# dw1000.net
KiCad netlist of a schematic drawn in Altium Designer
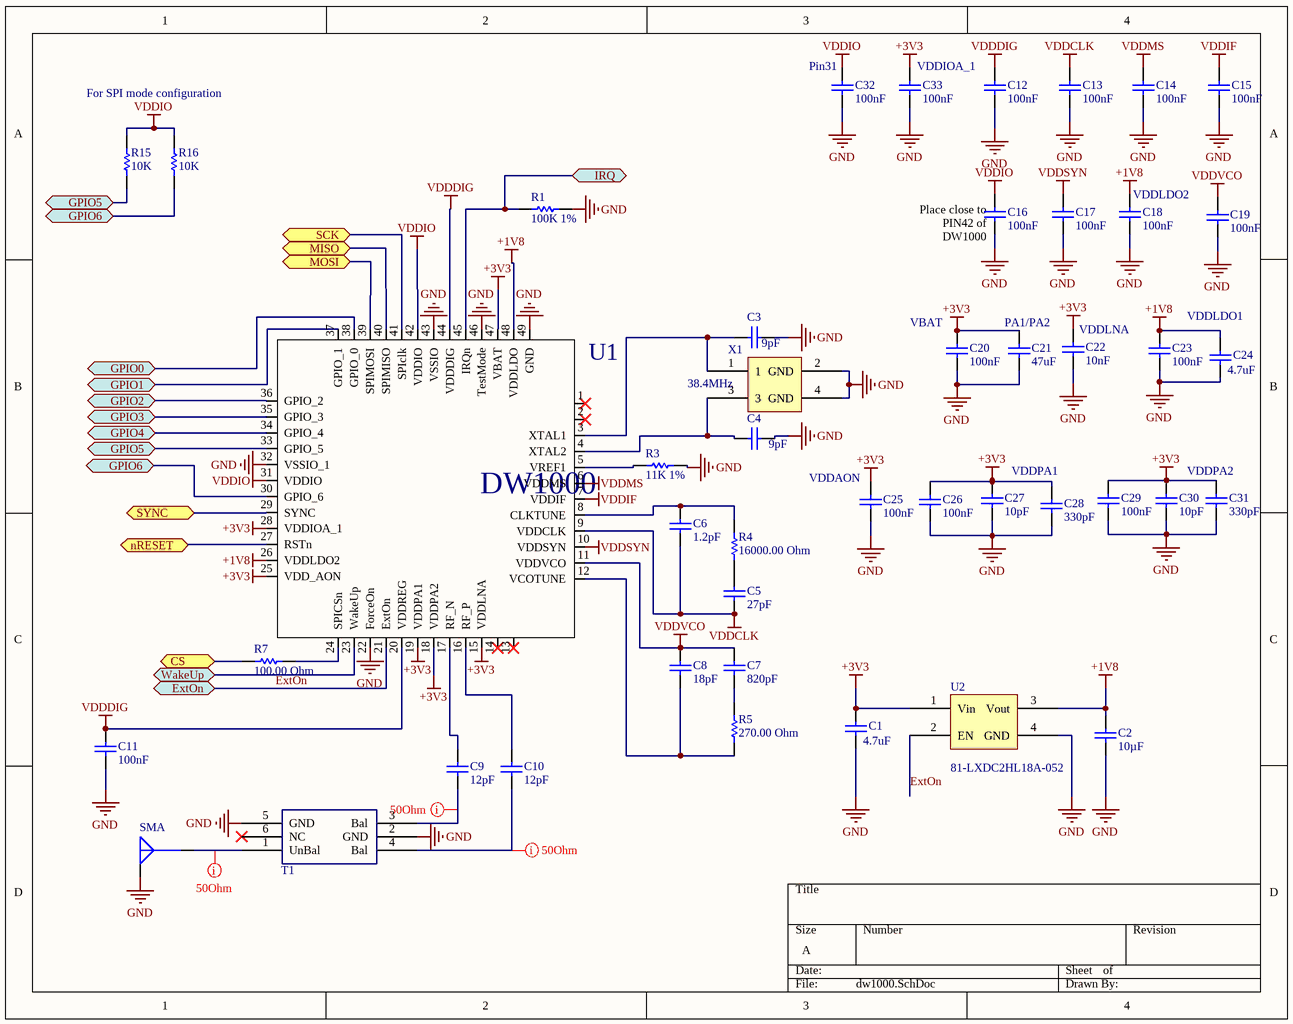
[diagram p0: dw1000.SchDoc]

(export (version "E")
  (design (tool "Eeschema 10.0.6"))
  (components
    (comp (ref "C1")
      (value "4.7uF")
      (footprint "CAPC0603(1608)100_M")
      (description "CAP 4.7uF 6.3V ±10% 0603 (1608 Metric) Thickness 1mm SMD")
      (fields (field (name "TOLERANCE") "Â±10%"))
      (libsource (lib "Altium Content Vault") (part "CMP-1035-02780-1"))
    )
    (comp (ref "C2")
      (value "10µF")
      (footprint "CAPC1608X100X35ML20T25")
      (fields (field (name "TOLERANCE") "±20%") (field (name "MANUFACTURER") "Taiyo Yuden"))
      (libsource (lib "Altium Content Vault") (part "CMP-2000-05443-1"))
    )
    (comp (ref "C3")
      (value "9pF")
      (footprint "CAPC0402(1005)60_L")
      (description "CAP 9pF 50V ±0.05pF 0402 (1005 Metric) Thickness 0.6mm SMD")
      (fields (field (name "TOLERANCE") "Â±0.05pF"))
      (libsource (lib "Altium Content Vault") (part "CAP"))
    )
    (comp (ref "C4")
      (value "9pF")
      (footprint "CAPC0402(1005)60_L")
      (description "CAP 9pF 50V ±0.05pF 0402 (1005 Metric) Thickness 0.6mm SMD")
      (fields (field (name "TOLERANCE") "Â±0.05pF"))
      (libsource (lib "Altium Content Vault") (part "CAP"))
    )
    (comp (ref "C5")
      (value "27pF")
      (footprint "CAPC0402(1005)60_L")
      (description "CAP 27pF 50V ±2% 0402 (1005 Metric) Thickness 0.6mm SMD")
      (fields (field (name "TOLERANCE") "Â±2%"))
      (libsource (lib "Altium Content Vault") (part "CMP-1034-00961-1"))
    )
    (comp (ref "C6")
      (value "1.2pF")
      (footprint "CAPC0402(1005)60_L")
      (description "CAP 1.2pF 50V ±0.05pF 0402 (1005 Metric) Thickness 0.6mm SMD")
      (fields (field (name "TOLERANCE") "Â±0.05pF"))
      (libsource (lib "Altium Content Vault") (part "CMP-1034-00083-1"))
    )
    (comp (ref "C7")
      (value "820pF")
      (footprint "CAPC0402(1005)60_L")
      (description "CAP 820pF 50V ±2% 0402 (1005 Metric) Thickness 0.6mm SMD")
      (fields (field (name "TOLERANCE") "Â±2%"))
      (libsource (lib "Altium Content Vault") (part "CMP-1034-01592-1"))
    )
    (comp (ref "C8")
      (value "18pF")
      (footprint "CAPC0402(1005)60_L")
      (description "CAP 18pF 50V ±2% 0402 (1005 Metric) Thickness 0.6mm SMD")
      (fields (field (name "TOLERANCE") "Â±2%"))
      (libsource (lib "Altium Content Vault") (part "CMP-1034-00863-1"))
    )
    (comp (ref "C9")
      (value "12pF")
      (footprint "CAPC0402(1005)60_L")
      (description "CAP 12pF 50V ±2% 0402 (1005 Metric) Thickness 0.6mm SMD")
      (fields (field (name "TOLERANCE") "Â±2%"))
      (libsource (lib "Altium Content Vault") (part "CAP"))
    )
    (comp (ref "C10")
      (value "12pF")
      (footprint "CAPC0402(1005)60_L")
      (description "CAP 12pF 50V ±2% 0402 (1005 Metric) Thickness 0.6mm SMD")
      (fields (field (name "TOLERANCE") "Â±2%"))
      (libsource (lib "Altium Content Vault") (part "CMP-1034-00768-1"))
    )
    (comp (ref "C11")
      (value "100nF")
      (footprint "CAPC0402(1005)60_L")
      (description "CAP 100nF 16V ±10% 0402 (1005 Metric) Thickness 0.6mm SMD")
      (fields (field (name "TOLERANCE") "Â±10%"))
      (libsource (lib "Altium Content Vault") (part "CMP-1034-02069-1"))
    )
    (comp (ref "C12")
      (value "100nF")
      (footprint "CAPC0402(1005)60_L")
      (description "CAP 100nF 16V ±10% 0402 (1005 Metric) Thickness 0.6mm SMD")
      (fields (field (name "TOLERANCE") "Â±10%"))
      (libsource (lib "Altium Content Vault") (part "CMP-1034-02069-1"))
    )
    (comp (ref "C13")
      (value "100nF")
      (footprint "CAPC0402(1005)60_L")
      (description "CAP 100nF 16V ±10% 0402 (1005 Metric) Thickness 0.6mm SMD")
      (fields (field (name "TOLERANCE") "Â±10%"))
      (libsource (lib "Altium Content Vault") (part "CMP-1034-02069-1"))
    )
    (comp (ref "C14")
      (value "100nF")
      (footprint "CAPC0402(1005)60_L")
      (description "CAP 100nF 16V ±10% 0402 (1005 Metric) Thickness 0.6mm SMD")
      (fields (field (name "TOLERANCE") "Â±10%"))
      (libsource (lib "Altium Content Vault") (part "CMP-1034-02069-1"))
    )
    (comp (ref "C15")
      (value "100nF")
      (footprint "CAPC0402(1005)60_L")
      (description "CAP 100nF 16V ±10% 0402 (1005 Metric) Thickness 0.6mm SMD")
      (fields (field (name "TOLERANCE") "Â±10%"))
      (libsource (lib "Altium Content Vault") (part "CMP-1034-02069-1"))
    )
    (comp (ref "C16")
      (value "100nF")
      (footprint "CAPC0402(1005)60_L")
      (description "CAP 100nF 16V ±10% 0402 (1005 Metric) Thickness 0.6mm SMD")
      (fields (field (name "TOLERANCE") "Â±10%"))
      (libsource (lib "Altium Content Vault") (part "CMP-1034-02069-1"))
    )
    (comp (ref "C17")
      (value "100nF")
      (footprint "CAPC0402(1005)60_L")
      (description "CAP 100nF 16V ±10% 0402 (1005 Metric) Thickness 0.6mm SMD")
      (fields (field (name "TOLERANCE") "Â±10%"))
      (libsource (lib "Altium Content Vault") (part "CMP-1034-02069-1"))
    )
    (comp (ref "C18")
      (value "100nF")
      (footprint "CAPC0402(1005)60_L")
      (description "CAP 100nF 16V ±10% 0402 (1005 Metric) Thickness 0.6mm SMD")
      (fields (field (name "TOLERANCE") "Â±10%"))
      (libsource (lib "Altium Content Vault") (part "CMP-1034-02069-1"))
    )
    (comp (ref "C19")
      (value "100nF")
      (footprint "CAPC0402(1005)60_L")
      (description "CAP 100nF 16V ±10% 0402 (1005 Metric) Thickness 0.6mm SMD")
      (fields (field (name "TOLERANCE") "Â±10%"))
      (libsource (lib "Altium Content Vault") (part "CMP-1034-02069-1"))
    )
    (comp (ref "C20")
      (value "100nF")
      (footprint "CAPC0402(1005)60_L")
      (description "CAP 100nF 16V ±10% 0402 (1005 Metric) Thickness 0.6mm SMD")
      (fields (field (name "TOLERANCE") "Â±10%"))
      (libsource (lib "Altium Content Vault") (part "CMP-1034-02069-1"))
    )
    (comp (ref "C21")
      (value "47uF")
      (footprint "CAPC0805(2012)145_L")
      (description "CAP 47uF 6.3V ±20% 0805 (2012 Metric) Thickness 1.45mm SMD")
      (fields (field (name "TOLERANCE") "Â±20%"))
      (libsource (lib "Altium Content Vault") (part "CMP-1036-04950-1"))
    )
    (comp (ref "C22")
      (value "10nF")
      (footprint "CAPC0402(1005)60_L")
      (description "CAP 10nF 25V ±10% 0402 (1005 Metric) Thickness 0.6mm SMD")
      (fields (field (name "TOLERANCE") "Â±10%"))
      (libsource (lib "Altium Content Vault") (part "CMP-1034-01880-1"))
    )
    (comp (ref "C23")
      (value "100nF")
      (footprint "CAPC0402(1005)60_L")
      (description "CAP 100nF 16V ±10% 0402 (1005 Metric) Thickness 0.6mm SMD")
      (fields (field (name "TOLERANCE") "Â±10%"))
      (libsource (lib "Altium Content Vault") (part "CMP-1034-02069-1"))
    )
    (comp (ref "C24")
      (value "4.7uF")
      (footprint "CAPC0603(1608)100_M")
      (description "CAP 4.7uF 6.3V ±10% 0603 (1608 Metric) Thickness 1mm SMD")
      (fields (field (name "TOLERANCE") "Â±10%"))
      (libsource (lib "Altium Content Vault") (part "CMP-1035-02780-1"))
    )
    (comp (ref "C25")
      (value "100nF")
      (footprint "CAPC0402(1005)60_L")
      (description "CAP 100nF 16V ±10% 0402 (1005 Metric) Thickness 0.6mm SMD")
      (fields (field (name "TOLERANCE") "Â±10%"))
      (libsource (lib "Altium Content Vault") (part "CMP-1034-02069-1"))
    )
    (comp (ref "C26")
      (value "100nF")
      (footprint "CAPC0402(1005)60_L")
      (description "CAP 100nF 16V ±10% 0402 (1005 Metric) Thickness 0.6mm SMD")
      (fields (field (name "TOLERANCE") "Â±10%"))
      (libsource (lib "Altium Content Vault") (part "CMP-1034-02069-1"))
    )
    (comp (ref "C27")
      (value "10pF")
      (footprint "CAPC0402(1005)60_L")
      (description "CAP 10pF 50V ±2% 0402 (1005 Metric) Thickness 0.6mm SMD")
      (fields (field (name "TOLERANCE") "Â±2%"))
      (libsource (lib "Altium Content Vault") (part "CMP-1034-00722-1"))
    )
    (comp (ref "C28")
      (value "330pF")
      (footprint "CAPC0402(1005)60_L")
      (description "CAP 330pF 50V ±2% 0402 (1005 Metric) Thickness 0.6mm SMD")
      (fields (field (name "TOLERANCE") "Â±2%"))
      (libsource (lib "Altium Content Vault") (part "CMP-1034-01432-1"))
    )
    (comp (ref "C29")
      (value "100nF")
      (footprint "CAPC0402(1005)60_L")
      (description "CAP 100nF 16V ±10% 0402 (1005 Metric) Thickness 0.6mm SMD")
      (fields (field (name "TOLERANCE") "Â±10%"))
      (libsource (lib "Altium Content Vault") (part "CMP-1034-02069-1"))
    )
    (comp (ref "C30")
      (value "10pF")
      (footprint "CAPC0402(1005)60_L")
      (description "CAP 10pF 50V ±2% 0402 (1005 Metric) Thickness 0.6mm SMD")
      (fields (field (name "TOLERANCE") "Â±2%"))
      (libsource (lib "Altium Content Vault") (part "CMP-1034-00722-1"))
    )
    (comp (ref "C31")
      (value "330pF")
      (footprint "CAPC0402(1005)60_L")
      (description "CAP 330pF 50V ±2% 0402 (1005 Metric) Thickness 0.6mm SMD")
      (fields (field (name "TOLERANCE") "Â±2%"))
      (libsource (lib "Altium Content Vault") (part "CMP-1034-01432-1"))
    )
    (comp (ref "C32")
      (value "100nF")
      (footprint "CAPC0402(1005)60_L")
      (description "CAP 100nF 16V ±10% 0402 (1005 Metric) Thickness 0.6mm SMD")
      (fields (field (name "TOLERANCE") "Â±10%"))
      (libsource (lib "Altium Content Vault") (part "CMP-1034-02069-1"))
    )
    (comp (ref "C33")
      (value "100nF")
      (footprint "CAPC0402(1005)60_L")
      (description "CAP 100nF 16V ±10% 0402 (1005 Metric) Thickness 0.6mm SMD")
      (fields (field (name "TOLERANCE") "Â±10%"))
      (libsource (lib "Altium Content Vault") (part "CMP-1034-02069-1"))
    )
    (comp (ref "R1")
      (value "100K 1%")
      (footprint "RESC0402(1005)_M")
      (description "100K 0.063W 1% 0402 (1005 Metric)  SMD")
      (fields (field (name "POWER") "0.063 W") (field (name "TOLERANCE") "1 %"))
      (libsource (lib "Altium Content Vault") (part "CMP-1011-00736-1"))
    )
    (comp (ref "R3")
      (value "11K 1%")
      (footprint "RESC0402(1005)_L")
      (description "11K 0.063W 1% 0402 (1005 Metric)  SMD")
      (fields (field (name "TOLERANCE") "1 %") (field (name "POWER") "0.063 W"))
      (libsource (lib "Altium Content Vault") (part "RES"))
    )
    (comp (ref "R4")
      (value "16000.00 Ohm")
      (footprint "RESC0402(1005)_L")
      (description "16K 0.063W 1% 0402 (1005 Metric)  SMD")
      (fields (field (name "POWER") "0.063 W") (field (name "TOLERANCE") "1 %"))
      (libsource (lib "Altium Content Vault") (part "CMP-1011-00644-1"))
    )
    (comp (ref "R5")
      (value "270.00 Ohm")
      (footprint "RESC0402(1005)_L")
      (description "270R 0.063W 1% 0402 (1005 Metric)  SMD")
      (fields (field (name "TOLERANCE") "1 %") (field (name "POWER") "0.063 W"))
      (libsource (lib "Altium Content Vault") (part "CMP-1011-00444-1"))
    )
    (comp (ref "R7")
      (value "100.00 Ohm")
      (footprint "RESC0402(1005)_L")
      (description "100R 0.063W 1% 0402 (1005 Metric)  SMD")
      (fields (field (name "TOLERANCE") "1 %") (field (name "POWER") "0.063 W"))
      (libsource (lib "Altium Content Vault") (part "CMP-1011-00397-1"))
    )
    (comp (ref "R15")
      (value "10K")
      (footprint "RESC0603(1608)_L")
      (description "10K 0.1W 5% 0603 (1608 Metric)  SMD")
      (fields (field (name "TOLERANCE") "5 %") (field (name "POWER") "0.1 W"))
      (libsource (lib "Altium Content Vault") (part "RES"))
    )
    (comp (ref "R16")
      (value "10K")
      (footprint "RESC0603(1608)_L")
      (description "10K 0.1W 5% 0603 (1608 Metric)  SMD")
      (fields (field (name "TOLERANCE") "5 %") (field (name "POWER") "0.1 W"))
      (libsource (lib "Altium Content Vault") (part "RES"))
    )
    (comp (ref "SMA")
      (value "0732511150")
      (footprint "sma_footprint")
      (description "CONN SMA JACK 50 OHM EDGE MNT")
      (fields (field (name "MANUFACTURER") "Molex, LLC"))
      (libsource (lib "Celestial Library Database") (part "RF Connector - SMA"))
    )
    (comp (ref "T1")
      (value "HHM1595A1")
      (footprint "hhm1595a1:HHM1595A1")
      (description "HHM1595A1 3000MHz - 8000MHz 0805")
      (libsource (lib "hhm1595a1") (part "HHM1595A1"))
    )
    (comp (ref "U1")
      (value "DW1000 IC")
      (footprint "DW1000:QFN-48")
      (description "UWB DW1000")
      (fields (field (name "PART NUMBER") "DW1000_QFN") (field (name "MANUFACTURER") "Decawave Ltd."))
      (libsource (lib "DW1000") (part "DW1000_QFN_48"))
    )
    (comp (ref "U2")
      (value "81-LXDC2HL18A-052")
      (footprint "PCBComponent_1")
      (fields (field (name "SUPPLIER PART NUMBER 1") "81-LXDC2HL18A-052"))
      (libsource (lib "lxdc2hl_18a") (part "Component_1"))
    )
    (comp (ref "X1")
      (value "38.4MHz")
      (footprint "tsx_3225fp")
      (libsource (lib "tsx-3225") (part "Component_1"))
    )
  )
  (nets
    (net (code "1") (name "+1V8") (class "Default")
      (node (ref "C18") (pin "1") (pinfunction "1_1") (pintype "passive"))
      (node (ref "C2") (pin "1") (pinfunction "1_1") (pintype "passive"))
      (node (ref "C23") (pin "1") (pinfunction "1_1") (pintype "passive"))
      (node (ref "C24") (pin "2") (pinfunction "2_2") (pintype "passive"))
      (node (ref "U1") (pin "26") (pinfunction "VDDLDO2_26") (pintype "passive"))
      (node (ref "U1") (pin "48") (pinfunction "VDDLDO_48") (pintype "passive"))
      (node (ref "U2") (pin "3") (pinfunction "Vout_3") (pintype "passive"))
    )
    (net (code "2") (name "+3V3") (class "Default")
      (node (ref "C1") (pin "2") (pinfunction "2_2") (pintype "passive"))
      (node (ref "C20") (pin "1") (pinfunction "1_1") (pintype "passive"))
      (node (ref "C21") (pin "2") (pinfunction "2_2") (pintype "passive"))
      (node (ref "C22") (pin "1") (pinfunction "1_1") (pintype "passive"))
      (node (ref "C25") (pin "1") (pinfunction "1_1") (pintype "passive"))
      (node (ref "C26") (pin "1") (pinfunction "1_1") (pintype "passive"))
      (node (ref "C27") (pin "2") (pinfunction "2_2") (pintype "passive"))
      (node (ref "C28") (pin "1") (pinfunction "1_1") (pintype "passive"))
      (node (ref "C29") (pin "1") (pinfunction "1_1") (pintype "passive"))
      (node (ref "C30") (pin "2") (pinfunction "2_2") (pintype "passive"))
      (node (ref "C31") (pin "1") (pinfunction "1_1") (pintype "passive"))
      (node (ref "C33") (pin "1") (pinfunction "1_1") (pintype "passive"))
      (node (ref "U1") (pin "15") (pinfunction "VDDLNA_15") (pintype "passive"))
      (node (ref "U1") (pin "18") (pinfunction "VDDPA2_18") (pintype "passive"))
      (node (ref "U1") (pin "19") (pinfunction "VDDPA1_19") (pintype "passive"))
      (node (ref "U1") (pin "25") (pinfunction "VDD_AON_25") (pintype "passive"))
      (node (ref "U1") (pin "28") (pinfunction "VDDIOA_1_28") (pintype "passive"))
      (node (ref "U1") (pin "47") (pinfunction "VBAT_47") (pintype "passive"))
      (node (ref "U2") (pin "1") (pinfunction "Vin_1") (pintype "passive"))
    )
    (net (code "3") (name "/CS") (class "Default")
      (node (ref "R7") (pin "2") (pinfunction "2_2") (pintype "passive"))
    )
    (net (code "4") (name "/ExtOn") (class "Default")
      (node (ref "U1") (pin "21") (pinfunction "ExtOn_21") (pintype "passive"))
      (node (ref "U2") (pin "2") (pinfunction "EN_2") (pintype "passive"))
    )
    (net (code "5") (name "/GPIO0") (class "Default")
      (node (ref "U1") (pin "38") (pinfunction "GPIO_0_38") (pintype "bidirectional"))
    )
    (net (code "6") (name "/GPIO1") (class "Default")
      (node (ref "U1") (pin "37") (pinfunction "GPIO_1_37") (pintype "bidirectional"))
    )
    (net (code "7") (name "/GPIO2") (class "Default")
      (node (ref "U1") (pin "36") (pinfunction "GPIO_2_36") (pintype "bidirectional"))
    )
    (net (code "8") (name "/GPIO3") (class "Default")
      (node (ref "U1") (pin "35") (pinfunction "GPIO_3_35") (pintype "bidirectional"))
    )
    (net (code "9") (name "/GPIO4") (class "Default")
      (node (ref "U1") (pin "34") (pinfunction "GPIO_4_34") (pintype "bidirectional"))
    )
    (net (code "10") (name "/GPIO5") (class "Default")
      (node (ref "R15") (pin "1") (pinfunction "1_1") (pintype "passive"))
      (node (ref "U1") (pin "33") (pinfunction "GPIO_5_33") (pintype "bidirectional"))
    )
    (net (code "11") (name "/GPIO6") (class "Default")
      (node (ref "R16") (pin "1") (pinfunction "1_1") (pintype "passive"))
      (node (ref "U1") (pin "30") (pinfunction "GPIO_6_30") (pintype "passive"))
    )
    (net (code "12") (name "/IRQ") (class "Default")
      (node (ref "R1") (pin "1") (pinfunction "1_1") (pintype "passive"))
      (node (ref "U1") (pin "45") (pinfunction "IRQn_45") (pintype "passive"))
    )
    (net (code "13") (name "/MISO") (class "Default")
      (node (ref "U1") (pin "40") (pinfunction "SPIMISO_40") (pintype "passive"))
    )
    (net (code "14") (name "/MOSI") (class "Default")
      (node (ref "U1") (pin "39") (pinfunction "SPIMOSI_39") (pintype "passive"))
    )
    (net (code "15") (name "/SCK") (class "Default")
      (node (ref "U1") (pin "41") (pinfunction "SPIclk_41") (pintype "passive"))
    )
    (net (code "16") (name "/SYNC") (class "Default")
      (node (ref "U1") (pin "29") (pinfunction "SYNC_29") (pintype "passive"))
    )
    (net (code "17") (name "/WakeUp") (class "Default")
      (node (ref "U1") (pin "23") (pinfunction "WakeUp_23") (pintype "passive"))
    )
    (net (code "18") (name "/nRESET") (class "Default")
      (node (ref "U1") (pin "27") (pinfunction "RSTn_27") (pintype "passive"))
    )
    (net (code "19") (name "GND") (class "Default")
      (node (ref "C1") (pin "1") (pinfunction "1_1") (pintype "passive"))
      (node (ref "C11") (pin "2") (pinfunction "2_2") (pintype "passive"))
      (node (ref "C12") (pin "2") (pinfunction "2_2") (pintype "passive"))
      (node (ref "C13") (pin "2") (pinfunction "2_2") (pintype "passive"))
      (node (ref "C14") (pin "2") (pinfunction "2_2") (pintype "passive"))
      (node (ref "C15") (pin "2") (pinfunction "2_2") (pintype "passive"))
      (node (ref "C16") (pin "2") (pinfunction "2_2") (pintype "passive"))
      (node (ref "C17") (pin "2") (pinfunction "2_2") (pintype "passive"))
      (node (ref "C18") (pin "2") (pinfunction "2_2") (pintype "passive"))
      (node (ref "C19") (pin "2") (pinfunction "2_2") (pintype "passive"))
      (node (ref "C2") (pin "2") (pinfunction "2_2") (pintype "passive"))
      (node (ref "C20") (pin "2") (pinfunction "2_2") (pintype "passive"))
      (node (ref "C21") (pin "1") (pinfunction "1_1") (pintype "passive"))
      (node (ref "C22") (pin "2") (pinfunction "2_2") (pintype "passive"))
      (node (ref "C23") (pin "2") (pinfunction "2_2") (pintype "passive"))
      (node (ref "C24") (pin "1") (pinfunction "1_1") (pintype "passive"))
      (node (ref "C25") (pin "2") (pinfunction "2_2") (pintype "passive"))
      (node (ref "C26") (pin "2") (pinfunction "2_2") (pintype "passive"))
      (node (ref "C27") (pin "1") (pinfunction "1_1") (pintype "passive"))
      (node (ref "C28") (pin "2") (pinfunction "2_2") (pintype "passive"))
      (node (ref "C29") (pin "2") (pinfunction "2_2") (pintype "passive"))
      (node (ref "C3") (pin "2") (pinfunction "2_2") (pintype "passive"))
      (node (ref "C30") (pin "1") (pinfunction "1_1") (pintype "passive"))
      (node (ref "C31") (pin "2") (pinfunction "2_2") (pintype "passive"))
      (node (ref "C32") (pin "2") (pinfunction "2_2") (pintype "passive"))
      (node (ref "C33") (pin "2") (pinfunction "2_2") (pintype "passive"))
      (node (ref "C4") (pin "2") (pinfunction "2_2") (pintype "passive"))
      (node (ref "R1") (pin "2") (pinfunction "2_2") (pintype "passive"))
      (node (ref "R3") (pin "2") (pinfunction "2_2") (pintype "passive"))
      (node (ref "SMA") (pin "G") (pinfunction "G_G") (pintype "passive"))
      (node (ref "T1") (pin "2") (pinfunction "GND_2") (pintype "passive"))
      (node (ref "T1") (pin "5") (pinfunction "GND_5") (pintype "passive"))
      (node (ref "U1") (pin "22") (pinfunction "ForceOn_22") (pintype "passive"))
      (node (ref "U1") (pin "32") (pinfunction "VSSIO_1_32") (pintype "passive"))
      (node (ref "U1") (pin "43") (pinfunction "VSSIO_43") (pintype "passive"))
      (node (ref "U1") (pin "46") (pinfunction "TestMode_46") (pintype "passive"))
      (node (ref "U1") (pin "49") (pinfunction "GND_49") (pintype "passive"))
      (node (ref "U2") (pin "4") (pinfunction "GND_4") (pintype "passive"))
      (node (ref "X1") (pin "2") (pinfunction "GND_2") (pintype "passive"))
      (node (ref "X1") (pin "4") (pinfunction "GND_4") (pintype "passive"))
    )
    (net (code "20") (name "Net-(C5-Pad1)") (class "Default")
      (node (ref "C5") (pin "1") (pinfunction "1_1") (pintype "passive"))
      (node (ref "R4") (pin "2") (pinfunction "2_2") (pintype "passive"))
    )
    (net (code "21") (name "Net-(C7-Pad2)") (class "Default")
      (node (ref "C7") (pin "2") (pinfunction "2_2") (pintype "passive"))
      (node (ref "R5") (pin "1") (pinfunction "1_1") (pintype "passive"))
    )
    (net (code "22") (name "Net-(C9-Pad2)") (class "Default")
      (node (ref "C9") (pin "2") (pinfunction "2_2") (pintype "passive"))
      (node (ref "T1") (pin "3") (pinfunction "Bal_3") (pintype "passive"))
    )
    (net (code "23") (name "Net-(C10-Pad2)") (class "Default")
      (node (ref "C10") (pin "2") (pinfunction "2_2") (pintype "passive"))
      (node (ref "T1") (pin "4") (pinfunction "Bal_4") (pintype "passive"))
    )
    (net (code "24") (name "Net-(T1-UnBal)") (class "Default")
      (node (ref "SMA") (pin "S") (pinfunction "S_S") (pintype "passive"))
      (node (ref "T1") (pin "1") (pinfunction "UnBal_1") (pintype "passive"))
    )
    (net (code "25") (name "Net-(U1-CLKTUNE)") (class "Default")
      (node (ref "C6") (pin "1") (pinfunction "1_1") (pintype "passive"))
      (node (ref "R4") (pin "1") (pinfunction "1_1") (pintype "passive"))
      (node (ref "U1") (pin "8") (pinfunction "CLKTUNE_8") (pintype "passive"))
    )
    (net (code "26") (name "Net-(U1-RF_N)") (class "Default")
      (node (ref "C9") (pin "1") (pinfunction "1_1") (pintype "passive"))
      (node (ref "U1") (pin "17") (pinfunction "RF_N_17") (pintype "passive"))
    )
    (net (code "27") (name "Net-(U1-RF_P)") (class "Default")
      (node (ref "C10") (pin "1") (pinfunction "1_1") (pintype "passive"))
      (node (ref "U1") (pin "16") (pinfunction "RF_P_16") (pintype "passive"))
    )
    (net (code "28") (name "Net-(U1-SPICSn)") (class "Default")
      (node (ref "R7") (pin "1") (pinfunction "1_1") (pintype "passive"))
      (node (ref "U1") (pin "24") (pinfunction "SPICSn_24") (pintype "passive"))
    )
    (net (code "29") (name "Net-(U1-VCOTUNE)") (class "Default")
      (node (ref "C8") (pin "1") (pinfunction "1_1") (pintype "passive"))
      (node (ref "R5") (pin "2") (pinfunction "2_2") (pintype "passive"))
      (node (ref "U1") (pin "12") (pinfunction "VCOTUNE_12") (pintype "passive"))
    )
    (net (code "30") (name "Net-(U1-VREF1)") (class "Default")
      (node (ref "R3") (pin "1") (pinfunction "1_1") (pintype "passive"))
      (node (ref "U1") (pin "5") (pinfunction "VREF1_5") (pintype "passive"))
    )
    (net (code "31") (name "Net-(U1-XTAL1)") (class "Default")
      (node (ref "C3") (pin "1") (pinfunction "1_1") (pintype "passive"))
      (node (ref "U1") (pin "3") (pinfunction "XTAL1_3") (pintype "passive"))
      (node (ref "X1") (pin "1") (pinfunction "1_1") (pintype "passive"))
    )
    (net (code "32") (name "Net-(U1-XTAL2)") (class "Default")
      (node (ref "C4") (pin "1") (pinfunction "1_1") (pintype "passive"))
      (node (ref "U1") (pin "4") (pinfunction "XTAL2_4") (pintype "passive"))
      (node (ref "X1") (pin "3") (pinfunction "3_3") (pintype "passive"))
    )
    (net (code "33") (name "VDDCLK") (class "Default")
      (node (ref "C13") (pin "1") (pinfunction "1_1") (pintype "passive"))
      (node (ref "C5") (pin "2") (pinfunction "2_2") (pintype "passive"))
      (node (ref "C6") (pin "2") (pinfunction "2_2") (pintype "passive"))
      (node (ref "U1") (pin "9") (pinfunction "VDDCLK_9") (pintype "passive"))
    )
    (net (code "34") (name "VDDDIG") (class "Default")
      (node (ref "C11") (pin "1") (pinfunction "1_1") (pintype "passive"))
      (node (ref "C12") (pin "1") (pinfunction "1_1") (pintype "passive"))
      (node (ref "U1") (pin "20") (pinfunction "VDDREG_20") (pintype "passive"))
      (node (ref "U1") (pin "44") (pinfunction "VDDDIG_44") (pintype "passive"))
    )
    (net (code "35") (name "VDDIF") (class "Default")
      (node (ref "C15") (pin "1") (pinfunction "1_1") (pintype "passive"))
      (node (ref "U1") (pin "7") (pinfunction "VDDIF_7") (pintype "passive"))
    )
    (net (code "36") (name "VDDIO") (class "Default")
      (node (ref "C16") (pin "1") (pinfunction "1_1") (pintype "passive"))
      (node (ref "C32") (pin "1") (pinfunction "1_1") (pintype "passive"))
      (node (ref "R15") (pin "2") (pinfunction "2_2") (pintype "passive"))
      (node (ref "R16") (pin "2") (pinfunction "2_2") (pintype "passive"))
      (node (ref "U1") (pin "31") (pinfunction "VDDIO_31") (pintype "passive"))
      (node (ref "U1") (pin "42") (pinfunction "VDDIO_42") (pintype "passive"))
    )
    (net (code "37") (name "VDDMS") (class "Default")
      (node (ref "C14") (pin "1") (pinfunction "1_1") (pintype "passive"))
      (node (ref "U1") (pin "6") (pinfunction "VDDMS_6") (pintype "passive"))
    )
    (net (code "38") (name "VDDSYN") (class "Default")
      (node (ref "C17") (pin "1") (pinfunction "1_1") (pintype "passive"))
      (node (ref "U1") (pin "10") (pinfunction "VDDSYN_10") (pintype "passive"))
    )
    (net (code "39") (name "VDDVCO") (class "Default")
      (node (ref "C19") (pin "1") (pinfunction "1_1") (pintype "passive"))
      (node (ref "C7") (pin "1") (pinfunction "1_1") (pintype "passive"))
      (node (ref "C8") (pin "2") (pinfunction "2_2") (pintype "passive"))
      (node (ref "U1") (pin "11") (pinfunction "VDDVCO_11") (pintype "passive"))
    )
    (net (code "40") (name "unconnected-(T1-NC-Pad6)") (class "Default")
      (node (ref "T1") (pin "6") (pinfunction "NC_6") (pintype "passive+no_connect"))
    )
    (net (code "41") (name "unconnected-(U1-Pad1)") (class "Default")
      (node (ref "U1") (pin "1") (pintype "passive+no_connect"))
    )
    (net (code "42") (name "unconnected-(U1-Pad2)") (class "Default")
      (node (ref "U1") (pin "2") (pintype "passive+no_connect"))
    )
    (net (code "43") (name "unconnected-(U1-Pad13)") (class "Default")
      (node (ref "U1") (pin "13") (pintype "passive+no_connect"))
    )
    (net (code "44") (name "unconnected-(U1-Pad14)") (class "Default")
      (node (ref "U1") (pin "14") (pintype "passive+no_connect"))
    )
  )
)
